# camera_timelapse.net
KiCad netlist of a schematic drawn in Altium Designer
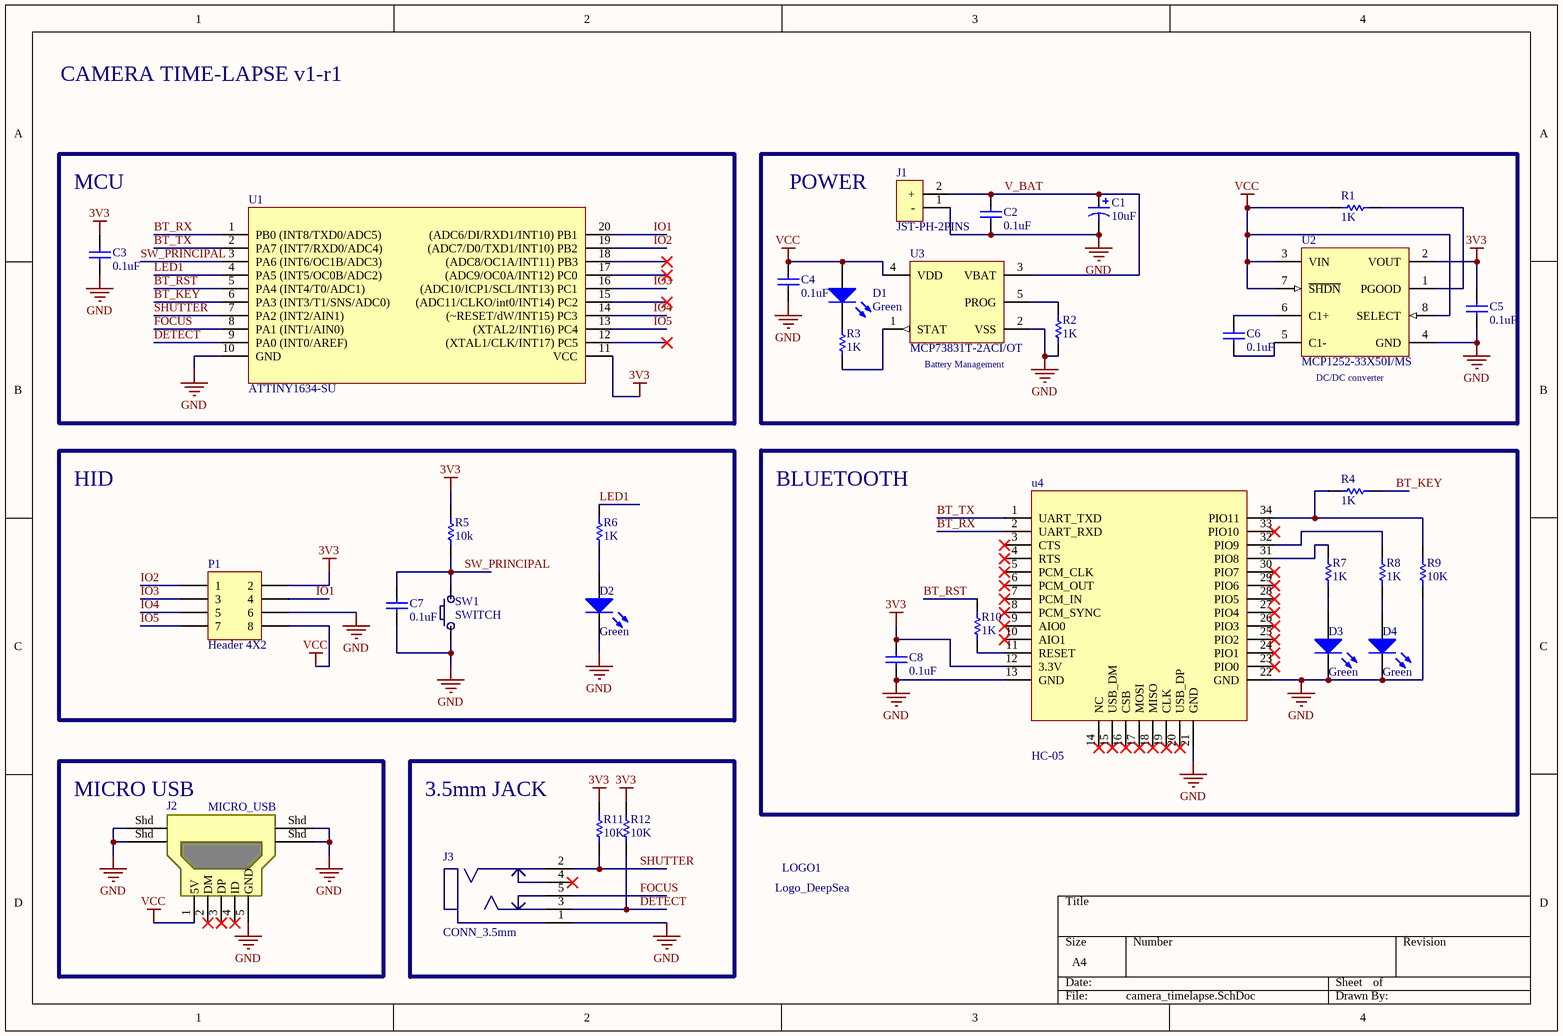
[diagram p0: camera_timelapse.SchDoc]

(export (version "E")
  (design (tool "Eeschema 10.0.6"))
  (components
    (comp (ref "C1") (value "10uF") (footprint "C_TANT_A_3216_N") (libsource (lib "General") (part "CP_SMD")))
    (comp (ref "C2") (value "0.1uF") (footprint "C0603_N") (libsource (lib "General") (part "C_SMD")))
    (comp (ref "C3") (value "0.1uF") (footprint "C0603_N") (libsource (lib "General") (part "C_SMD")))
    (comp (ref "C4") (value "0.1uF") (footprint "C0603_N") (libsource (lib "General") (part "C_SMD")))
    (comp (ref "C5") (value "0.1uF") (footprint "C0603_N") (libsource (lib "General") (part "C_SMD")))
    (comp (ref "C6") (value "0.1uF") (footprint "C0603_N") (libsource (lib "General") (part "C_SMD")))
    (comp (ref "C7") (value "0.1uF") (footprint "C0603_N") (libsource (lib "General") (part "C_SMD")))
    (comp (ref "C8") (value "0.1uF") (footprint "C0603_N") (libsource (lib "General") (part "C_SMD")))
    (comp (ref "D1")
      (value "Green")
      (footprint "R0603_N")
      (fields (field (name "COLOR") "Green"))
      (libsource (lib "discrete") (part "LED_SMD"))
    )
    (comp (ref "D2")
      (value "Green")
      (footprint "R0603_N")
      (fields (field (name "COLOR") "Green"))
      (libsource (lib "discrete") (part "LED_SMD"))
    )
    (comp (ref "D3")
      (value "Green")
      (footprint "R0603_N")
      (fields (field (name "COLOR") "Green"))
      (libsource (lib "discrete") (part "LED_SMD"))
    )
    (comp (ref "D4")
      (value "Green")
      (footprint "R0603_N")
      (fields (field (name "COLOR") "Green"))
      (libsource (lib "discrete") (part "LED_SMD"))
    )
    (comp (ref "J1")
      (value "JST-PH-2PINS")
      (footprint "JST-PH-2")
      (description "CONN HEADER PH SIDE 2POS 2MM SMD")
      (fields
        (field (name "MANUFACTURER") "JST Sales America Inc")
        (field (name "MANUFACTURER PART NUMBER") "S2B-PH-SM4-TB(LF)(SN)")
      )
      (libsource (lib "General") (part "JST-PH-2PINS"))
    )
    (comp (ref "J2")
      (value "MICRO_USB")
      (footprint "USB MICRO")
      (description "CONN USB MICRO B RECPT SMT R/A")
      (fields (field (name "MANUFACTURER") "FCI") (field (name "MANUFACTURER PART NUMBER") "10118194-0001LF"))
      (libsource (lib "General") (part "MICRO_USB"))
    )
    (comp (ref "J3")
      (value "CONN_3.5mm")
      (footprint "JACK_3.5MM")
      (description "CONN JACK STEREO 3.5MM SMD")
      (fields
        (field (name "MANUFACTURER") "Switchcraft Inc.")
        (field (name "MANUFACTURER PART NUMBER") "35RASMT4BHNTRX")
      )
      (libsource (lib "General") (part "CONN_3.5mm"))
    )
    (comp (ref "LOGO1")
      (value "Logo_DeepSea")
      (footprint "DeepSea_logo1")
      (libsource (lib "General") (part "Logo_DeepSea"))
    )
    (comp (ref "P1")
      (value "Header 4X2")
      (footprint "HDR2X4")
      (description "Header, 4-Pin, Dual row")
      (fields (field (name "PUBLISHER") "Altium Limited"))
      (libsource (lib "Miscellaneous Connectors") (part "Header 4X2"))
    )
    (comp (ref "R1") (value "1K") (footprint "R0603_N") (libsource (lib "discrete") (part "R_SMD")))
    (comp (ref "R2") (value "1K") (footprint "R0603_N") (libsource (lib "discrete") (part "R_SMD")))
    (comp (ref "R3") (value "1K") (footprint "R0603_N") (libsource (lib "discrete") (part "R_SMD")))
    (comp (ref "R4") (value "1K") (footprint "R0603_N") (libsource (lib "discrete") (part "R_SMD")))
    (comp (ref "R5") (value "10k") (footprint "R0603_N") (libsource (lib "discrete") (part "R_SMD")))
    (comp (ref "R6") (value "1K") (footprint "R0603_N") (libsource (lib "discrete") (part "R_SMD")))
    (comp (ref "R7") (value "1K") (footprint "R0603_N") (libsource (lib "discrete") (part "R_SMD")))
    (comp (ref "R8") (value "1K") (footprint "R0603_N") (libsource (lib "discrete") (part "R_SMD")))
    (comp (ref "R9") (value "10K") (footprint "R0603_N") (libsource (lib "discrete") (part "R_SMD")))
    (comp (ref "R10") (value "1K") (footprint "R0603_N") (libsource (lib "discrete") (part "R_SMD")))
    (comp (ref "R11") (value "10K") (footprint "R0603_N") (libsource (lib "discrete") (part "R_SMD")))
    (comp (ref "R12") (value "10K") (footprint "R0603_N") (libsource (lib "discrete") (part "R_SMD")))
    (comp (ref "SW1")
      (value "SWITCH")
      (footprint "swich_foot")
      (description "SWITCH TACTILE SPST-NO 0.05A 12V")
      (fields
        (field (name "MANUFACTURER") "TE Connectivity")
        (field (name "MANUFACTURER PART NUMBER") "FSM4JSMATR")
      )
      (libsource (lib "General") (part "SWITCH"))
    )
    (comp (ref "U1")
      (value "ATTINY1634-SU")
      (footprint "SOIC20_L")
      (description "IC MCU 8BIT 16KB FLASH 20SOIC")
      (fields (field (name "MANUFACTURER") "Atmel"))
      (libsource (lib "General") (part "ATTINY1634-SU"))
    )
    (comp (ref "U2")
      (value "MCP1252-33X50I/MS")
      (footprint "MSOP-MS8_L")
      (description "IC REG MULTI CONFIG 0.12A 8MSOP")
      (fields (field (name "MANUFACTURER") "Microchip Technology"))
      (libsource (lib "General") (part "MCP1252-33X50I/MS"))
    )
    (comp (ref "U3")
      (value "MCP73831T-2ACI/OT")
      (footprint "SOT-23-OT5_M")
      (description "IC CONTROLLR LI-ION 4.2V SOT23-5")
      (fields (field (name "MANUFACTURER") "Microchip Technology"))
      (libsource (lib "General") (part "MCP73831T-2ACI/OT"))
    )
    (comp (ref "u4")
      (value "HC-05")
      (footprint "HC-05")
      (description "Bluetooth RS232 module")
      (libsource (lib "General") (part "HC-05"))
    )
  )
  (nets
    (net (code "1") (name "/BT_KEY") (class "Default")
      (node (ref "R4") (pin "1") (pinfunction "1_1") (pintype "passive"))
      (node (ref "U1") (pin "6") (pinfunction "PA3_(INT3/T1/SNS/ADC0)_6") (pintype "passive"))
    )
    (net (code "2") (name "/BT_RST") (class "Default")
      (node (ref "R10") (pin "1") (pinfunction "1_1") (pintype "passive"))
      (node (ref "U1") (pin "5") (pinfunction "PA4_(INT4/T0/ADC1)_5") (pintype "passive"))
    )
    (net (code "3") (name "/BT_RX") (class "Default")
      (node (ref "U1") (pin "1") (pinfunction "PB0_(INT8/TXD0/ADC5)_1") (pintype "passive"))
      (node (ref "u4") (pin "2") (pinfunction "UART_RXD_2") (pintype "passive"))
    )
    (net (code "4") (name "/BT_TX") (class "Default")
      (node (ref "U1") (pin "2") (pinfunction "PA7_(INT7/RXD0/ADC4)_2") (pintype "passive"))
      (node (ref "u4") (pin "1") (pinfunction "UART_TXD_1") (pintype "passive"))
    )
    (net (code "5") (name "/DETECT") (class "Default")
      (node (ref "J3") (pin "3") (pintype "passive"))
      (node (ref "R12") (pin "2") (pinfunction "2_2") (pintype "passive"))
      (node (ref "U1") (pin "9") (pinfunction "PA0_(INT0/AREF)_9") (pintype "passive"))
    )
    (net (code "6") (name "/FOCUS") (class "Default")
      (node (ref "J3") (pin "5") (pintype "passive"))
      (node (ref "U1") (pin "8") (pinfunction "PA1_(INT1/AIN0)_8") (pintype "passive"))
    )
    (net (code "7") (name "/IO1") (class "Default")
      (node (ref "P1") (pin "4") (pinfunction "4_4") (pintype "passive"))
      (node (ref "U1") (pin "20") (pinfunction "(ADC6/DI/RXD1/INT10)_PB1_20") (pintype "passive"))
    )
    (net (code "8") (name "/IO2") (class "Default")
      (node (ref "P1") (pin "1") (pinfunction "1_1") (pintype "passive"))
      (node (ref "U1") (pin "19") (pinfunction "(ADC7/D0/TXD1/INT10)_PB2_19") (pintype "passive"))
    )
    (net (code "9") (name "/IO3") (class "Default")
      (node (ref "P1") (pin "3") (pinfunction "3_3") (pintype "passive"))
      (node (ref "U1") (pin "16") (pinfunction "(ADC10/ICP1/SCL/INT13)_PC1_16") (pintype "passive"))
    )
    (net (code "10") (name "/IO4") (class "Default")
      (node (ref "P1") (pin "5") (pinfunction "5_5") (pintype "passive"))
      (node (ref "U1") (pin "14") (pinfunction "(~RESET/dW/INT15)_PC3_14") (pintype "passive"))
    )
    (net (code "11") (name "/IO5") (class "Default")
      (node (ref "P1") (pin "7") (pinfunction "7_7") (pintype "passive"))
      (node (ref "U1") (pin "13") (pinfunction "(XTAL2/INT16)_PC4_13") (pintype "passive"))
    )
    (net (code "12") (name "/LED1") (class "Default")
      (node (ref "R6") (pin "1") (pinfunction "1_1") (pintype "passive"))
      (node (ref "U1") (pin "4") (pinfunction "PA5_(INT5/OC0B/ADC2)_4") (pintype "passive"))
    )
    (net (code "13") (name "/SHUTTER") (class "Default")
      (node (ref "J3") (pin "2") (pintype "passive"))
      (node (ref "R11") (pin "2") (pinfunction "2_2") (pintype "passive"))
      (node (ref "U1") (pin "7") (pinfunction "PA2_(INT2/AIN1)_7") (pintype "passive"))
    )
    (net (code "14") (name "/SW_PRINCIPAL") (class "Default")
      (node (ref "C7") (pin "1") (pinfunction "1_1") (pintype "passive"))
      (node (ref "R5") (pin "1") (pinfunction "1_1") (pintype "passive"))
      (node (ref "SW1") (pin "2") (pinfunction "*_2") (pintype "passive"))
      (node (ref "U1") (pin "3") (pinfunction "PA6_(INT6/OC1B/ADC3)_3") (pintype "passive"))
    )
    (net (code "15") (name "/V_BAT") (class "Default")
      (node (ref "C1") (pin "1") (pinfunction "1_1") (pintype "passive"))
      (node (ref "C2") (pin "2") (pinfunction "2_2") (pintype "passive"))
      (node (ref "J1") (pin "2") (pinfunction "+_2") (pintype "passive"))
      (node (ref "U3") (pin "3") (pinfunction "VBAT_3") (pintype "power_in"))
    )
    (net (code "16") (name "3V3") (class "Default")
      (node (ref "C3") (pin "2") (pinfunction "2_2") (pintype "passive"))
      (node (ref "C5") (pin "2") (pinfunction "2_2") (pintype "passive"))
      (node (ref "C8") (pin "2") (pinfunction "2_2") (pintype "passive"))
      (node (ref "P1") (pin "2") (pinfunction "2_2") (pintype "passive"))
      (node (ref "R11") (pin "1") (pinfunction "1_1") (pintype "passive"))
      (node (ref "R12") (pin "1") (pinfunction "1_1") (pintype "passive"))
      (node (ref "R5") (pin "2") (pinfunction "2_2") (pintype "passive"))
      (node (ref "U1") (pin "11") (pinfunction "VCC_11") (pintype "passive"))
      (node (ref "U2") (pin "2") (pinfunction "VOUT_2") (pintype "power_in"))
      (node (ref "u4") (pin "12") (pinfunction "3.3V_12") (pintype "passive"))
    )
    (net (code "17") (name "GND") (class "Default")
      (node (ref "C1") (pin "2") (pinfunction "2_2") (pintype "passive"))
      (node (ref "C2") (pin "1") (pinfunction "1_1") (pintype "passive"))
      (node (ref "C3") (pin "1") (pinfunction "1_1") (pintype "passive"))
      (node (ref "C4") (pin "1") (pinfunction "1_1") (pintype "passive"))
      (node (ref "C5") (pin "1") (pinfunction "1_1") (pintype "passive"))
      (node (ref "C7") (pin "2") (pinfunction "2_2") (pintype "passive"))
      (node (ref "C8") (pin "1") (pinfunction "1_1") (pintype "passive"))
      (node (ref "D2") (pin "2") (pinfunction "K_2") (pintype "passive"))
      (node (ref "D3") (pin "2") (pinfunction "K_2") (pintype "passive"))
      (node (ref "D4") (pin "2") (pinfunction "K_2") (pintype "passive"))
      (node (ref "J1") (pin "1") (pinfunction "-_1") (pintype "passive"))
      (node (ref "J2") (pin "5") (pinfunction "GND_5") (pintype "power_in"))
      (node (ref "J2") (pin "Shd") (pinfunction "6_Shd") (pintype "passive"))
      (node (ref "J3") (pin "1") (pintype "passive"))
      (node (ref "P1") (pin "6") (pinfunction "6_6") (pintype "passive"))
      (node (ref "R2") (pin "1") (pinfunction "1_1") (pintype "passive"))
      (node (ref "R9") (pin "2") (pinfunction "2_2") (pintype "passive"))
      (node (ref "SW1") (pin "1") (pinfunction "*_1") (pintype "passive"))
      (node (ref "U1") (pin "10") (pinfunction "GND_10") (pintype "passive"))
      (node (ref "U2") (pin "4") (pinfunction "GND_4") (pintype "power_in"))
      (node (ref "U3") (pin "2") (pinfunction "VSS_2") (pintype "power_in"))
      (node (ref "u4") (pin "13") (pinfunction "GND_13") (pintype "passive"))
      (node (ref "u4") (pin "21") (pinfunction "GND_21") (pintype "passive"))
      (node (ref "u4") (pin "22") (pinfunction "GND_22") (pintype "passive"))
    )
    (net (code "18") (name "Net-(D1-K)") (class "Default")
      (node (ref "D1") (pin "2") (pinfunction "K_2") (pintype "passive"))
      (node (ref "R3") (pin "1") (pinfunction "1_1") (pintype "passive"))
    )
    (net (code "19") (name "Net-(D2-A)") (class "Default")
      (node (ref "D2") (pin "1") (pinfunction "A_1") (pintype "passive"))
      (node (ref "R6") (pin "2") (pinfunction "2_2") (pintype "passive"))
    )
    (net (code "20") (name "Net-(D3-A)") (class "Default")
      (node (ref "D3") (pin "1") (pinfunction "A_1") (pintype "passive"))
      (node (ref "R7") (pin "2") (pinfunction "2_2") (pintype "passive"))
    )
    (net (code "21") (name "Net-(D4-A)") (class "Default")
      (node (ref "D4") (pin "1") (pinfunction "A_1") (pintype "passive"))
      (node (ref "R8") (pin "2") (pinfunction "2_2") (pintype "passive"))
    )
    (net (code "22") (name "Net-(U2-C1+)") (class "Default")
      (node (ref "C6") (pin "2") (pinfunction "2_2") (pintype "passive"))
      (node (ref "U2") (pin "6") (pinfunction "C1+_6") (pintype "passive"))
    )
    (net (code "23") (name "Net-(U2-C1-)") (class "Default")
      (node (ref "C6") (pin "1") (pinfunction "1_1") (pintype "passive"))
      (node (ref "U2") (pin "5") (pinfunction "C1-_5") (pintype "passive"))
    )
    (net (code "24") (name "Net-(U2-PGOOD)") (class "Default")
      (node (ref "R1") (pin "1") (pinfunction "1_1") (pintype "passive"))
      (node (ref "U2") (pin "1") (pinfunction "PGOOD_1") (pintype "open_collector"))
    )
    (net (code "25") (name "Net-(U3-PROG)") (class "Default")
      (node (ref "R2") (pin "2") (pinfunction "2_2") (pintype "passive"))
      (node (ref "U3") (pin "5") (pinfunction "PROG_5") (pintype "passive"))
    )
    (net (code "26") (name "Net-(U3-STAT)") (class "Default")
      (node (ref "R3") (pin "2") (pinfunction "2_2") (pintype "passive"))
      (node (ref "U3") (pin "1") (pinfunction "STAT_1") (pintype "output"))
    )
    (net (code "27") (name "Net-(u4-PIO8)") (class "Default")
      (node (ref "R7") (pin "1") (pinfunction "1_1") (pintype "passive"))
      (node (ref "u4") (pin "31") (pinfunction "PIO8_31") (pintype "passive"))
    )
    (net (code "28") (name "Net-(u4-PIO9)") (class "Default")
      (node (ref "R8") (pin "1") (pinfunction "1_1") (pintype "passive"))
      (node (ref "u4") (pin "32") (pinfunction "PIO9_32") (pintype "passive"))
    )
    (net (code "29") (name "Net-(u4-PIO11)") (class "Default")
      (node (ref "R4") (pin "2") (pinfunction "2_2") (pintype "passive"))
      (node (ref "R9") (pin "1") (pinfunction "1_1") (pintype "passive"))
      (node (ref "u4") (pin "34") (pinfunction "PIO11_34") (pintype "passive"))
    )
    (net (code "30") (name "Net-(u4-RESET)") (class "Default")
      (node (ref "R10") (pin "2") (pinfunction "2_2") (pintype "passive"))
      (node (ref "u4") (pin "11") (pinfunction "RESET_11") (pintype "passive"))
    )
    (net (code "31") (name "VCC") (class "Default")
      (node (ref "C4") (pin "2") (pinfunction "2_2") (pintype "passive"))
      (node (ref "D1") (pin "1") (pinfunction "A_1") (pintype "passive"))
      (node (ref "J2") (pin "1") (pinfunction "5V_1") (pintype "power_in"))
      (node (ref "P1") (pin "8") (pinfunction "8_8") (pintype "passive"))
      (node (ref "R1") (pin "2") (pinfunction "2_2") (pintype "passive"))
      (node (ref "U2") (pin "3") (pinfunction "VIN_3") (pintype "power_in"))
      (node (ref "U2") (pin "7") (pinfunction "~{SHDN}_7") (pintype "input"))
      (node (ref "U2") (pin "8") (pinfunction "SELECT_8") (pintype "input"))
      (node (ref "U3") (pin "4") (pinfunction "VDD_4") (pintype "power_in"))
    )
    (net (code "32") (name "unconnected-(J2-DM-Pad2)") (class "Default")
      (node (ref "J2") (pin "2") (pinfunction "DM_2") (pintype "passive+no_connect"))
    )
    (net (code "33") (name "unconnected-(J2-DP-Pad3)") (class "Default")
      (node (ref "J2") (pin "3") (pinfunction "DP_3") (pintype "passive+no_connect"))
    )
    (net (code "34") (name "unconnected-(J2-ID-Pad4)") (class "Default")
      (node (ref "J2") (pin "4") (pinfunction "ID_4") (pintype "passive+no_connect"))
    )
    (net (code "35") (name "unconnected-(J3-Pad4)") (class "Default")
      (node (ref "J3") (pin "4") (pintype "passive+no_connect"))
    )
    (net (code "36") (name "unconnected-(U1-(ADC8{slash}OC1A{slash}INT11)_PB3-Pad18)") (class "Default")
      (node (ref "U1") (pin "18") (pinfunction "(ADC8/OC1A/INT11)_PB3_18") (pintype "passive+no_connect"))
    )
    (net (code "37") (name "unconnected-(U1-(ADC9{slash}OC0A{slash}INT12)_PC0-Pad17)") (class "Default")
      (node (ref "U1") (pin "17") (pinfunction "(ADC9/OC0A/INT12)_PC0_17") (pintype "passive+no_connect"))
    )
    (net (code "38") (name "unconnected-(U1-(ADC11{slash}CLKO{slash}int0{slash}INT14)_PC2-Pad15)") (class "Default")
      (node (ref "U1") (pin "15") (pinfunction "(ADC11/CLKO/int0/INT14)_PC2_15") (pintype "passive+no_connect"))
    )
    (net (code "39") (name "unconnected-(U1-(XTAL1{slash}CLK{slash}INT17)_PC5-Pad12)") (class "Default")
      (node (ref "U1") (pin "12") (pinfunction "(XTAL1/CLK/INT17)_PC5_12") (pintype "passive+no_connect"))
    )
    (net (code "40") (name "unconnected-(u4-AIO0-Pad9)") (class "Default")
      (node (ref "u4") (pin "9") (pinfunction "AIO0_9") (pintype "passive+no_connect"))
    )
    (net (code "41") (name "unconnected-(u4-AIO1-Pad10)") (class "Default")
      (node (ref "u4") (pin "10") (pinfunction "AIO1_10") (pintype "passive+no_connect"))
    )
    (net (code "42") (name "unconnected-(u4-CLK-Pad19)") (class "Default")
      (node (ref "u4") (pin "19") (pinfunction "CLK_19") (pintype "passive+no_connect"))
    )
    (net (code "43") (name "unconnected-(u4-CSB-Pad16)") (class "Default")
      (node (ref "u4") (pin "16") (pinfunction "CSB_16") (pintype "passive+no_connect"))
    )
    (net (code "44") (name "unconnected-(u4-CTS-Pad3)") (class "Default")
      (node (ref "u4") (pin "3") (pinfunction "CTS_3") (pintype "passive+no_connect"))
    )
    (net (code "45") (name "unconnected-(u4-MISO-Pad18)") (class "Default")
      (node (ref "u4") (pin "18") (pinfunction "MISO_18") (pintype "passive+no_connect"))
    )
    (net (code "46") (name "unconnected-(u4-MOSI-Pad17)") (class "Default")
      (node (ref "u4") (pin "17") (pinfunction "MOSI_17") (pintype "passive+no_connect"))
    )
    (net (code "47") (name "unconnected-(u4-NC-Pad14)") (class "Default")
      (node (ref "u4") (pin "14") (pinfunction "NC_14") (pintype "passive+no_connect"))
    )
    (net (code "48") (name "unconnected-(u4-PCM_CLK-Pad5)") (class "Default")
      (node (ref "u4") (pin "5") (pinfunction "PCM_CLK_5") (pintype "passive+no_connect"))
    )
    (net (code "49") (name "unconnected-(u4-PCM_IN-Pad7)") (class "Default")
      (node (ref "u4") (pin "7") (pinfunction "PCM_IN_7") (pintype "passive+no_connect"))
    )
    (net (code "50") (name "unconnected-(u4-PCM_OUT-Pad6)") (class "Default")
      (node (ref "u4") (pin "6") (pinfunction "PCM_OUT_6") (pintype "passive+no_connect"))
    )
    (net (code "51") (name "unconnected-(u4-PCM_SYNC-Pad8)") (class "Default")
      (node (ref "u4") (pin "8") (pinfunction "PCM_SYNC_8") (pintype "passive+no_connect"))
    )
    (net (code "52") (name "unconnected-(u4-PIO0-Pad23)") (class "Default")
      (node (ref "u4") (pin "23") (pinfunction "PIO0_23") (pintype "passive+no_connect"))
    )
    (net (code "53") (name "unconnected-(u4-PIO1-Pad24)") (class "Default")
      (node (ref "u4") (pin "24") (pinfunction "PIO1_24") (pintype "passive+no_connect"))
    )
    (net (code "54") (name "unconnected-(u4-PIO2-Pad25)") (class "Default")
      (node (ref "u4") (pin "25") (pinfunction "PIO2_25") (pintype "passive+no_connect"))
    )
    (net (code "55") (name "unconnected-(u4-PIO3-Pad26)") (class "Default")
      (node (ref "u4") (pin "26") (pinfunction "PIO3_26") (pintype "passive+no_connect"))
    )
    (net (code "56") (name "unconnected-(u4-PIO4-Pad27)") (class "Default")
      (node (ref "u4") (pin "27") (pinfunction "PIO4_27") (pintype "passive+no_connect"))
    )
    (net (code "57") (name "unconnected-(u4-PIO5-Pad28)") (class "Default")
      (node (ref "u4") (pin "28") (pinfunction "PIO5_28") (pintype "passive+no_connect"))
    )
    (net (code "58") (name "unconnected-(u4-PIO6-Pad29)") (class "Default")
      (node (ref "u4") (pin "29") (pinfunction "PIO6_29") (pintype "passive+no_connect"))
    )
    (net (code "59") (name "unconnected-(u4-PIO7-Pad30)") (class "Default")
      (node (ref "u4") (pin "30") (pinfunction "PIO7_30") (pintype "passive+no_connect"))
    )
    (net (code "60") (name "unconnected-(u4-PIO10-Pad33)") (class "Default")
      (node (ref "u4") (pin "33") (pinfunction "PIO10_33") (pintype "passive+no_connect"))
    )
    (net (code "61") (name "unconnected-(u4-RTS-Pad4)") (class "Default")
      (node (ref "u4") (pin "4") (pinfunction "RTS_4") (pintype "passive+no_connect"))
    )
    (net (code "62") (name "unconnected-(u4-USB_DM-Pad15)") (class "Default")
      (node (ref "u4") (pin "15") (pinfunction "USB_DM_15") (pintype "passive+no_connect"))
    )
    (net (code "63") (name "unconnected-(u4-USB_DP-Pad20)") (class "Default")
      (node (ref "u4") (pin "20") (pinfunction "USB_DP_20") (pintype "passive+no_connect"))
    )
  )
)
